# 0004.net
KiCad netlist of a schematic drawn in EasyEDA
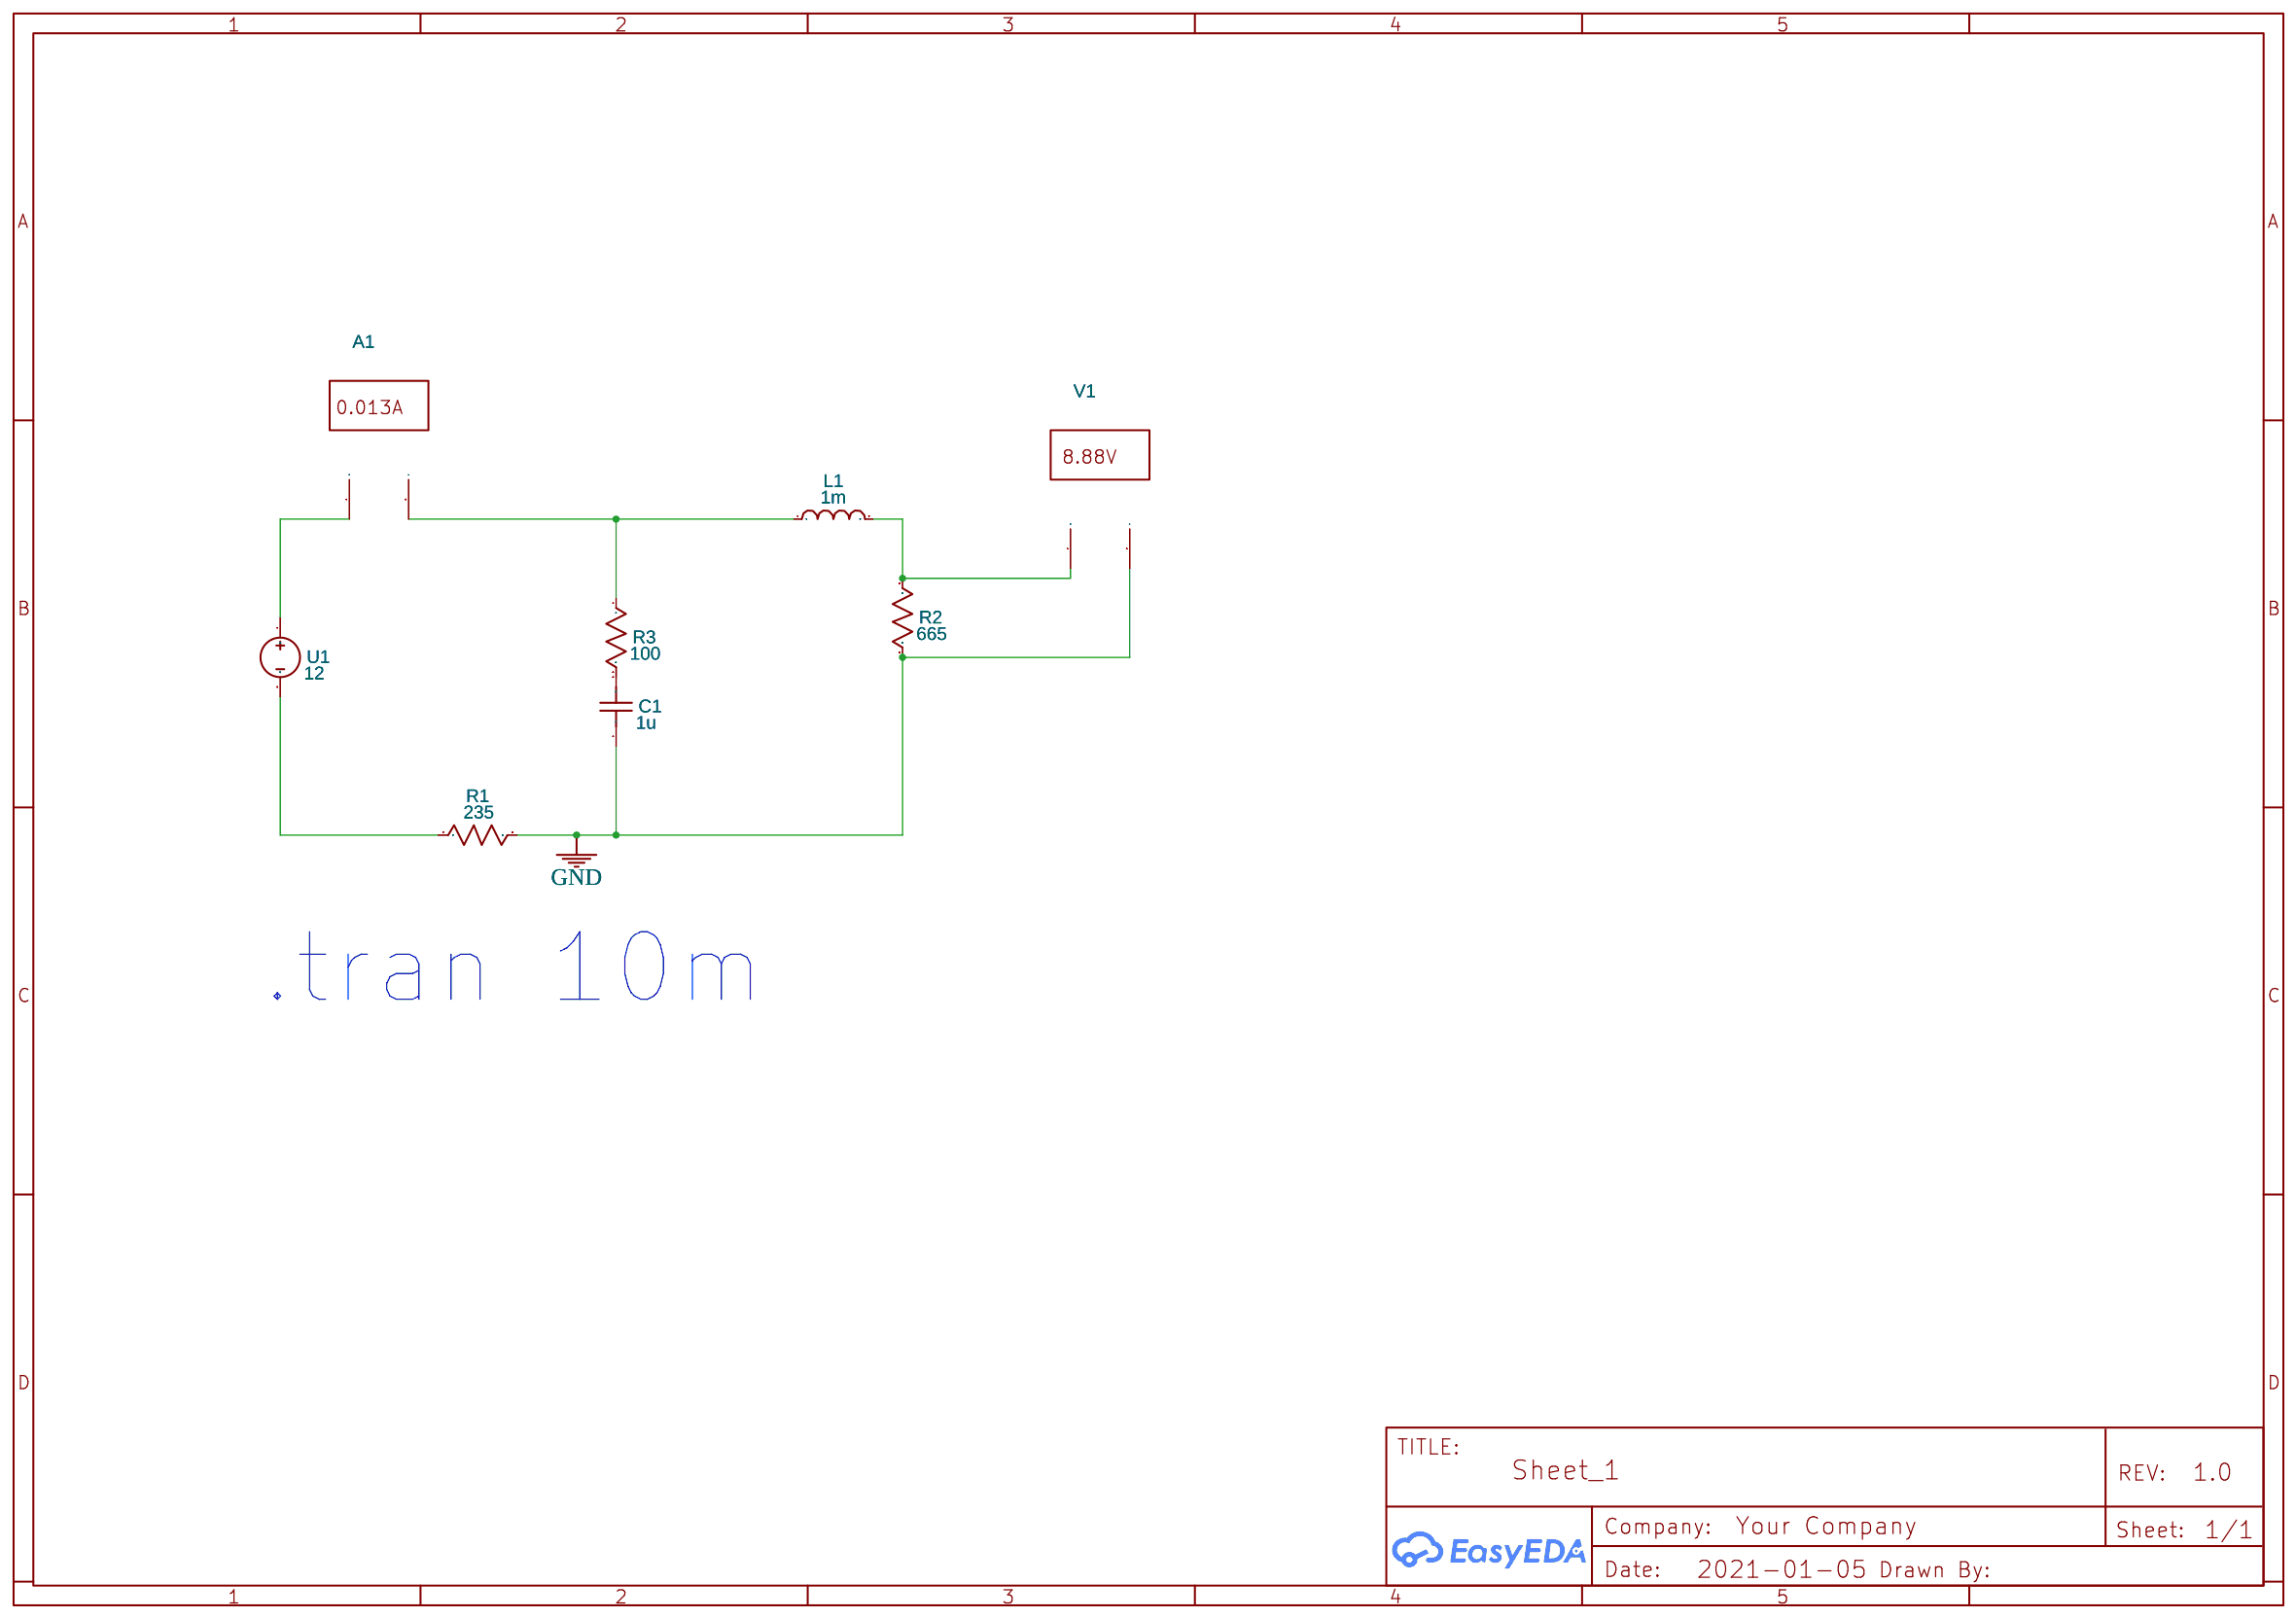
[diagram p0: schematic sheet]

(export (version "E")
  (design (tool "Eeschema 10.0.6"))
  (components
    (comp (ref "A1") (value "Multimeter") (libsource (lib "") (part "MULTIMETER")))
    (comp (ref "C1") (value "1u") (libsource (lib "") (part "Capacitor_US")))
    (comp (ref "L1") (value "1m") (libsource (lib "") (part "Inductor")))
    (comp (ref "R1") (value "235") (libsource (lib "") (part "Resistor_US")))
    (comp (ref "R2") (value "665") (libsource (lib "") (part "Resistor_US_1")))
    (comp (ref "R3") (value "100") (libsource (lib "") (part "Resistor_US_1")))
    (comp (ref "U1") (value "12") (libsource (lib "") (part "VDC")))
    (comp (ref "V1") (value "Multimeter") (libsource (lib "") (part "MULTIMETER_1")))
  )
  (nets
    (net (code "1") (name "GND") (class "Default")
      (node (ref "C1") (pin "1") (pinfunction "1_1") (pintype "unspecified"))
      (node (ref "R1") (pin "2") (pinfunction "2_2") (pintype "unspecified"))
      (node (ref "R2") (pin "2") (pinfunction "2_2") (pintype "unspecified"))
      (node (ref "V1") (pin "2") (pinfunction "I_2") (pintype "unspecified"))
    )
    (net (code "2") (name "Net-(A1-+)") (class "Default")
      (node (ref "A1") (pin "1") (pinfunction "+_1") (pintype "unspecified"))
      (node (ref "U1") (pin "1") (pinfunction "1_1") (pintype "unspecified"))
    )
    (net (code "3") (name "Net-(A1-I)") (class "Default")
      (node (ref "A1") (pin "2") (pinfunction "I_2") (pintype "unspecified"))
      (node (ref "L1") (pin "1") (pinfunction "1_1") (pintype "unspecified"))
      (node (ref "R3") (pin "1") (pinfunction "1_1") (pintype "unspecified"))
    )
    (net (code "4") (name "Net-(R1-Pad1)") (class "Default")
      (node (ref "R1") (pin "1") (pinfunction "1_1") (pintype "unspecified"))
      (node (ref "U1") (pin "2") (pinfunction "2_2") (pintype "unspecified"))
    )
    (net (code "5") (name "Net-(V1-+)") (class "Default")
      (node (ref "L1") (pin "2") (pinfunction "2_2") (pintype "unspecified"))
      (node (ref "R2") (pin "1") (pinfunction "1_1") (pintype "unspecified"))
      (node (ref "V1") (pin "1") (pinfunction "+_1") (pintype "unspecified"))
    )
    (net (code "6") (name "unconnected-(C1-Pad2)") (class "Default")
      (node (ref "C1") (pin "2") (pinfunction "2_2") (pintype "unspecified"))
    )
    (net (code "7") (name "unconnected-(R3-Pad2)") (class "Default")
      (node (ref "R3") (pin "2") (pinfunction "2_2") (pintype "unspecified"))
    )
  )
)
